# SCH_balcony_pump_2022-12-04.net
KiCad netlist of a schematic drawn in EasyEDA
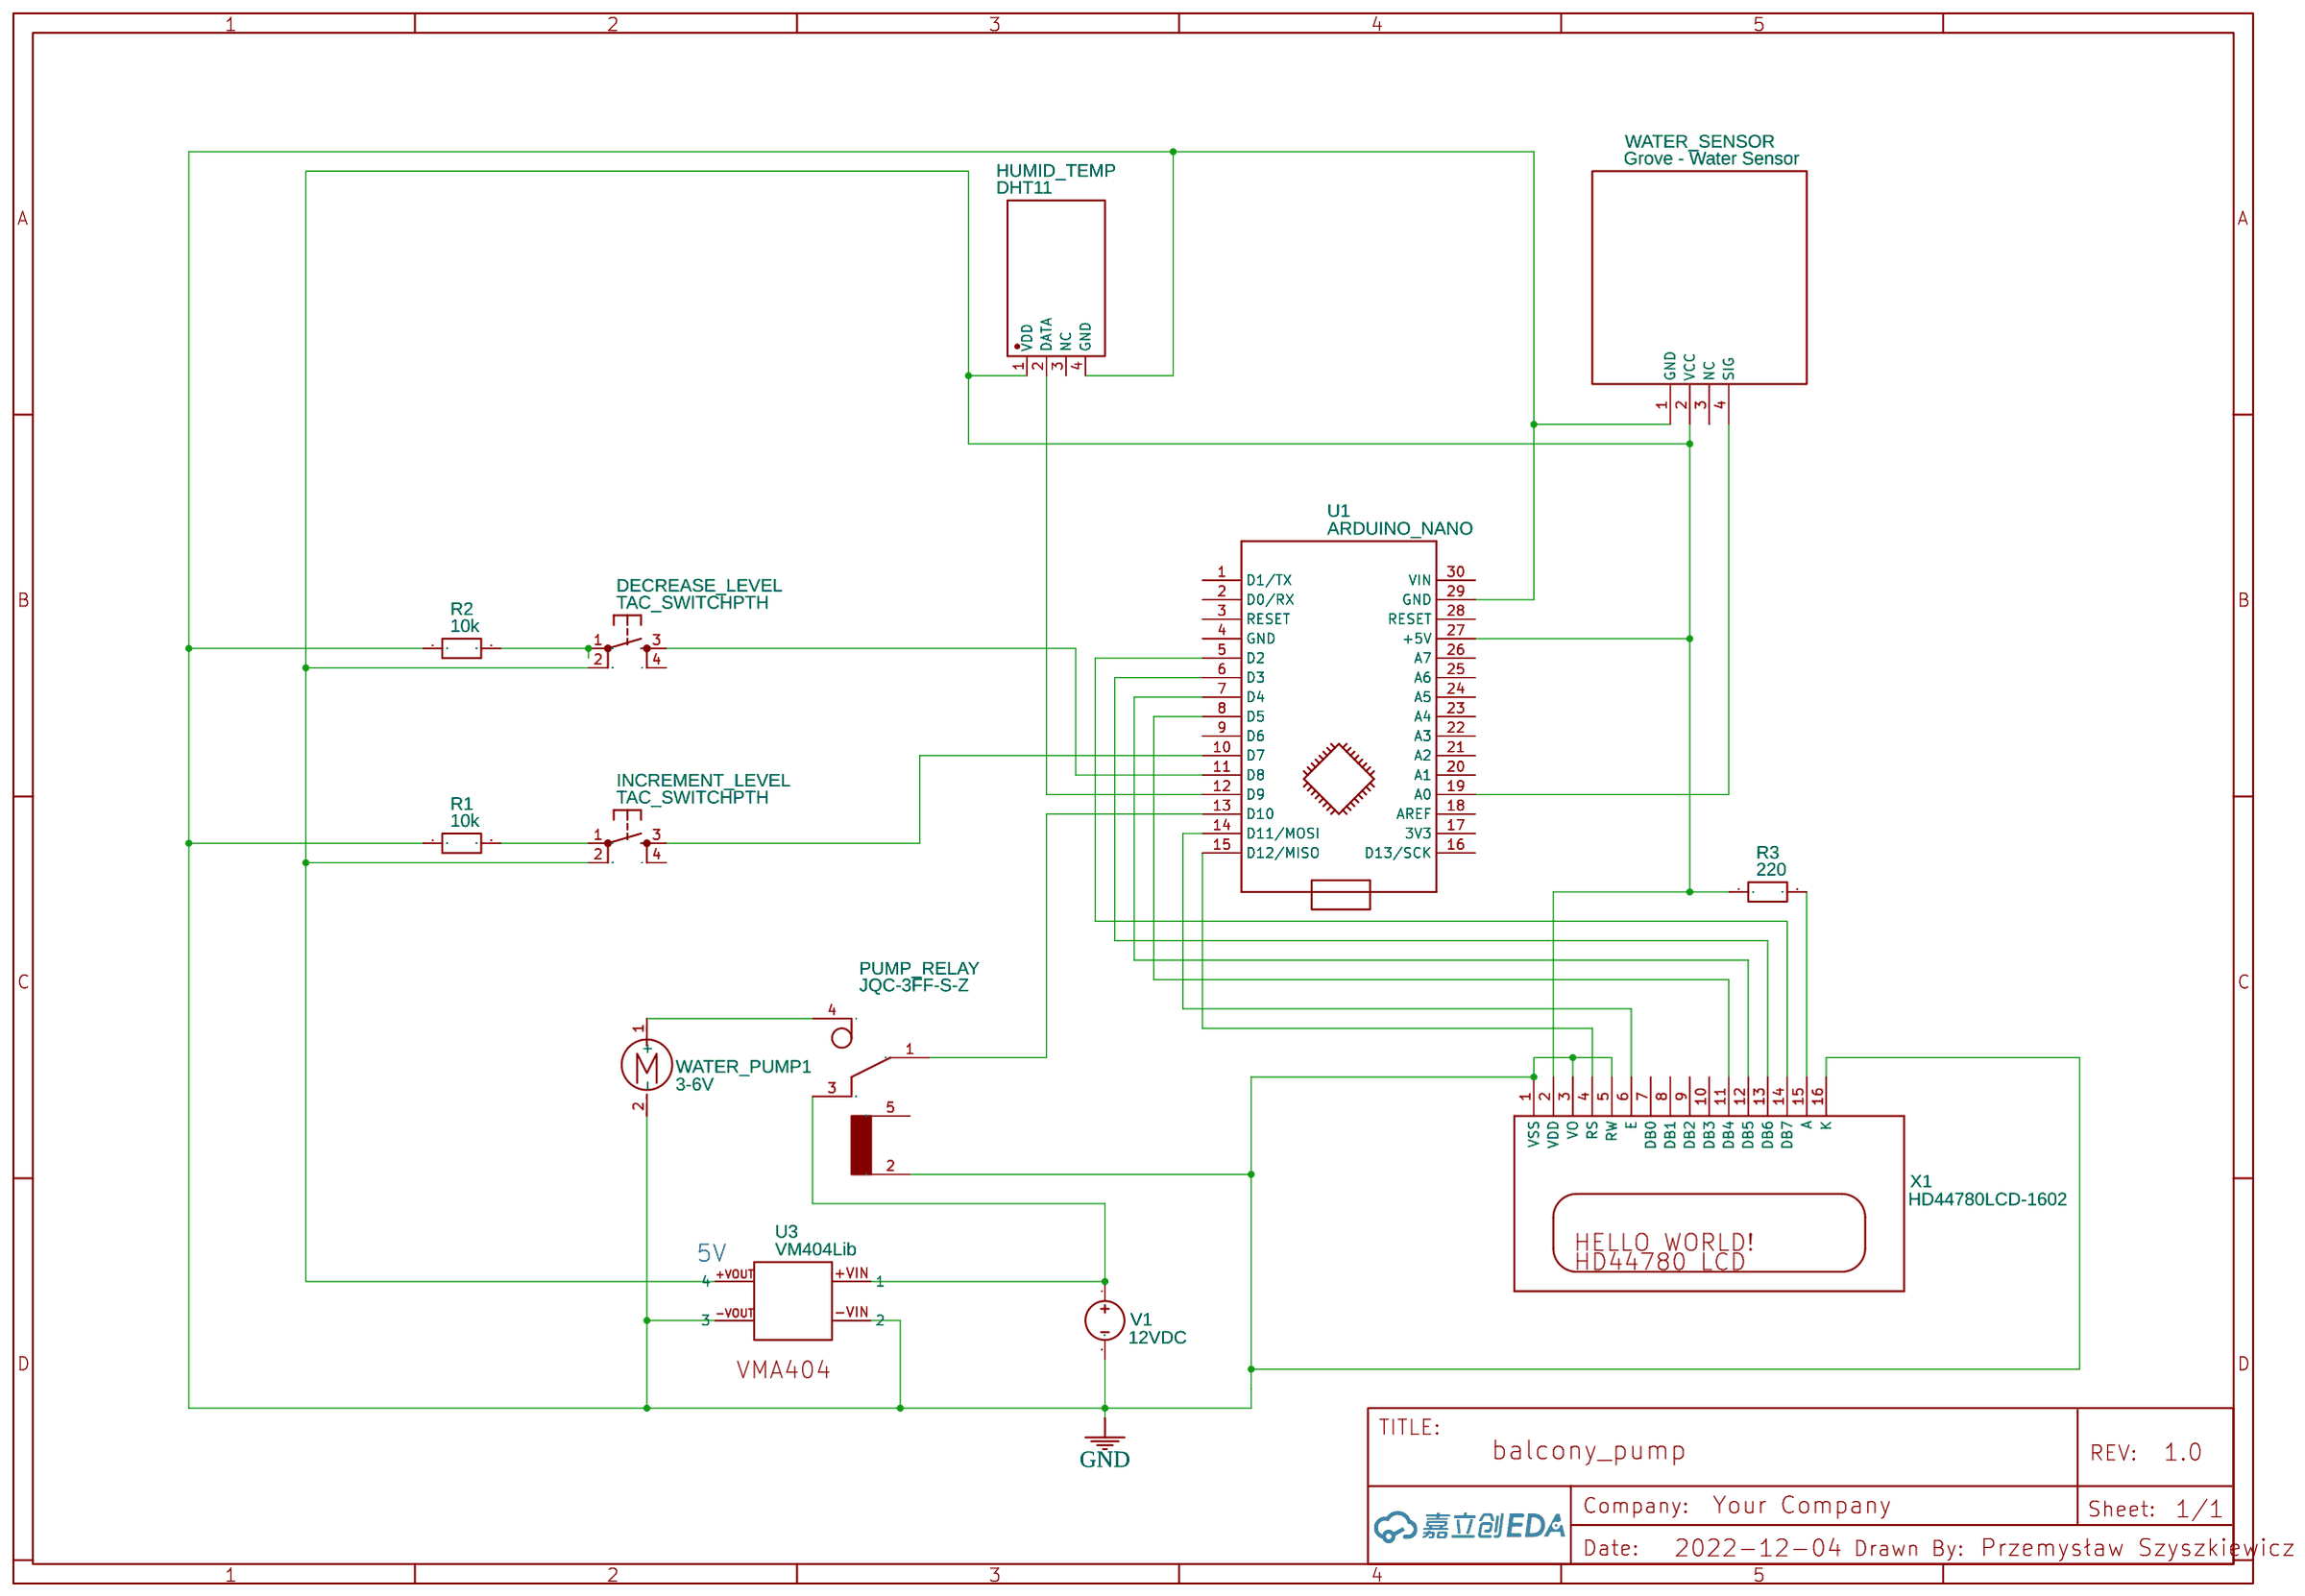
[diagram p0: schematic sheet]

(export (version "E")
  (design (tool "Eeschema 10.0.6"))
  (components
    (comp (ref "DECREASE_LEVEL") (value "TAC_SWITCHPTH") (libsource (lib "") (part "TAC_SWITCHPTH_1")))
    (comp (ref "HUMID_TEMP")
      (value "DHT11")
      (fields (field (name "BOM_Supplier Part") "C117051"))
      (libsource (lib "") (part "DHT11"))
    )
    (comp (ref "INCREMENT_LEVEL") (value "TAC_SWITCHPTH") (libsource (lib "") (part "TAC_SWITCHPTH")))
    (comp (ref "PUMP_RELAY") (value "JQC-3FF-S-Z") (libsource (lib "") (part "JQC-3FF-S-Z")))
    (comp (ref "R1") (value "10k") (libsource (lib "") (part "R_0603_EU")))
    (comp (ref "R2") (value "10k") (libsource (lib "") (part "R_0603_EU")))
    (comp (ref "R3") (value "220") (libsource (lib "") (part "R_0603_EU")))
    (comp (ref "U1") (value "ARDUINO_NANO") (libsource (lib "") (part "ARDUINO_NANO")))
    (comp (ref "U3")
      (value "VM404Lib")
      (fields
        (field (name "BOM_Manufacturer Part") "New SchematicLib")
        (field (name "BOM_Supplier Part") "1612753")
      )
      (libsource (lib "") (part "VM404Lib"))
    )
    (comp (ref "V1") (value "12VDC") (libsource (lib "") (part "Power_Supply_12V")))
    (comp (ref "WATER_PUMP1") (value "3-6V") (libsource (lib "") (part "Motor_DC")))
    (comp (ref "WATER_SENSOR")
      (value "Grove - Water Sensor")
      (fields (field (name "BOM_Supplier Part") "undefined"))
      (libsource (lib "") (part "Grove - Water Sensor"))
    )
    (comp (ref "X1") (value "HD44780LCD-1602") (libsource (lib "") (part "HD44780LCD-1602")))
  )
  (nets
    (net (code "1") (name "GND") (class "Default")
      (node (ref "HUMID_TEMP") (pin "4") (pinfunction "GND_4") (pintype "unspecified"))
      (node (ref "PUMP_RELAY") (pin "2") (pinfunction "2_2") (pintype "unspecified"))
      (node (ref "R1") (pin "1") (pinfunction "1_1") (pintype "unspecified"))
      (node (ref "R2") (pin "1") (pinfunction "1_1") (pintype "unspecified"))
      (node (ref "U1") (pin "29") (pinfunction "GND_29") (pintype "unspecified"))
      (node (ref "U3") (pin "-VIN") (pinfunction "2_-VIN") (pintype "unspecified"))
      (node (ref "U3") (pin "-VOUT") (pinfunction "3_-VOUT") (pintype "unspecified"))
      (node (ref "V1") (pin "2") (pinfunction "2_2") (pintype "unspecified"))
      (node (ref "WATER_PUMP1") (pin "2") (pinfunction "-_2") (pintype "unspecified"))
      (node (ref "WATER_SENSOR") (pin "1") (pinfunction "GND_1") (pintype "unspecified"))
      (node (ref "X1") (pin "1") (pinfunction "VSS_1") (pintype "unspecified"))
      (node (ref "X1") (pin "16") (pinfunction "K_16") (pintype "input"))
      (node (ref "X1") (pin "3") (pinfunction "VO_3") (pintype "input"))
      (node (ref "X1") (pin "5") (pinfunction "RW_5") (pintype "input"))
    )
    (net (code "2") (name "Net-(DECREASE_LEVEL-Pad1)") (class "Default")
      (node (ref "DECREASE_LEVEL") (pin "1") (pinfunction "1_1") (pintype "unspecified"))
      (node (ref "R2") (pin "2") (pinfunction "2_2") (pintype "unspecified"))
    )
    (net (code "3") (name "Net-(HUMID_TEMP-DATA)") (class "Default")
      (node (ref "HUMID_TEMP") (pin "2") (pinfunction "DATA_2") (pintype "unspecified"))
      (node (ref "U1") (pin "12") (pinfunction "D9_12") (pintype "unspecified"))
    )
    (net (code "4") (name "Net-(HUMID_TEMP-VDD)") (class "Default")
      (node (ref "DECREASE_LEVEL") (pin "2") (pinfunction "2_2") (pintype "unspecified"))
      (node (ref "HUMID_TEMP") (pin "1") (pinfunction "VDD_1") (pintype "unspecified"))
      (node (ref "INCREMENT_LEVEL") (pin "2") (pinfunction "2_2") (pintype "unspecified"))
      (node (ref "R3") (pin "1") (pinfunction "1_1") (pintype "unspecified"))
      (node (ref "U1") (pin "27") (pinfunction "+5V_27") (pintype "unspecified"))
      (node (ref "U3") (pin "+VOUT") (pinfunction "4_+VOUT") (pintype "unspecified"))
      (node (ref "WATER_SENSOR") (pin "2") (pinfunction "VCC_2") (pintype "unspecified"))
      (node (ref "X1") (pin "2") (pinfunction "VDD_2") (pintype "unspecified"))
    )
    (net (code "5") (name "Net-(INCREMENT_LEVEL-Pad1)") (class "Default")
      (node (ref "INCREMENT_LEVEL") (pin "1") (pinfunction "1_1") (pintype "unspecified"))
      (node (ref "R1") (pin "2") (pinfunction "2_2") (pintype "unspecified"))
    )
    (net (code "6") (name "Net-(U1-A0)") (class "Default")
      (node (ref "U1") (pin "19") (pinfunction "A0_19") (pintype "unspecified"))
      (node (ref "WATER_SENSOR") (pin "4") (pinfunction "SIG_4") (pintype "unspecified"))
    )
    (net (code "7") (name "Net-(U1-D2)") (class "Default")
      (node (ref "U1") (pin "5") (pinfunction "D2_5") (pintype "unspecified"))
      (node (ref "X1") (pin "14") (pinfunction "DB7_14") (pintype "unspecified"))
    )
    (net (code "8") (name "Net-(U1-D3)") (class "Default")
      (node (ref "U1") (pin "6") (pinfunction "D3_6") (pintype "unspecified"))
      (node (ref "X1") (pin "13") (pinfunction "DB6_13") (pintype "unspecified"))
    )
    (net (code "9") (name "Net-(U1-D4)") (class "Default")
      (node (ref "U1") (pin "7") (pinfunction "D4_7") (pintype "unspecified"))
      (node (ref "X1") (pin "12") (pinfunction "DB5_12") (pintype "unspecified"))
    )
    (net (code "10") (name "Net-(U1-D5)") (class "Default")
      (node (ref "U1") (pin "8") (pinfunction "D5_8") (pintype "unspecified"))
      (node (ref "X1") (pin "11") (pinfunction "DB4_11") (pintype "unspecified"))
    )
    (net (code "11") (name "Net-(U1-D7)") (class "Default")
      (node (ref "INCREMENT_LEVEL") (pin "3") (pinfunction "3_3") (pintype "unspecified"))
      (node (ref "U1") (pin "10") (pinfunction "D7_10") (pintype "unspecified"))
    )
    (net (code "12") (name "Net-(U1-D8)") (class "Default")
      (node (ref "DECREASE_LEVEL") (pin "3") (pinfunction "3_3") (pintype "unspecified"))
      (node (ref "U1") (pin "11") (pinfunction "D8_11") (pintype "unspecified"))
    )
    (net (code "13") (name "Net-(U1-D10)") (class "Default")
      (node (ref "PUMP_RELAY") (pin "1") (pinfunction "1_1") (pintype "unspecified"))
      (node (ref "U1") (pin "13") (pinfunction "D10_13") (pintype "unspecified"))
    )
    (net (code "14") (name "Net-(U1-D11{slash}MOSI)") (class "Default")
      (node (ref "U1") (pin "14") (pinfunction "D11/MOSI_14") (pintype "unspecified"))
      (node (ref "X1") (pin "6") (pinfunction "E_6") (pintype "input"))
    )
    (net (code "15") (name "Net-(U1-D12{slash}MISO)") (class "Default")
      (node (ref "U1") (pin "15") (pinfunction "D12/MISO_15") (pintype "unspecified"))
      (node (ref "X1") (pin "4") (pinfunction "RS_4") (pintype "input"))
    )
    (net (code "16") (name "Net-(U3-1)") (class "Default")
      (node (ref "PUMP_RELAY") (pin "3") (pinfunction "3_3") (pintype "unspecified"))
      (node (ref "U3") (pin "+VIN") (pinfunction "1_+VIN") (pintype "unspecified"))
      (node (ref "V1") (pin "1") (pinfunction "1_1") (pintype "unspecified"))
    )
    (net (code "17") (name "Net-(WATER_PUMP1-+)") (class "Default")
      (node (ref "PUMP_RELAY") (pin "4") (pinfunction "4_4") (pintype "unspecified"))
      (node (ref "WATER_PUMP1") (pin "1") (pinfunction "+_1") (pintype "unspecified"))
    )
    (net (code "18") (name "Net-(X1-A)") (class "Default")
      (node (ref "R3") (pin "2") (pinfunction "2_2") (pintype "unspecified"))
      (node (ref "X1") (pin "15") (pinfunction "A_15") (pintype "input"))
    )
    (net (code "19") (name "unconnected-(DECREASE_LEVEL-Pad4)") (class "Default")
      (node (ref "DECREASE_LEVEL") (pin "4") (pinfunction "4_4") (pintype "unspecified"))
    )
    (net (code "20") (name "unconnected-(HUMID_TEMP-NC-Pad3)") (class "Default")
      (node (ref "HUMID_TEMP") (pin "3") (pinfunction "NC_3") (pintype "unspecified"))
    )
    (net (code "21") (name "unconnected-(INCREMENT_LEVEL-Pad4)") (class "Default")
      (node (ref "INCREMENT_LEVEL") (pin "4") (pinfunction "4_4") (pintype "unspecified"))
    )
    (net (code "22") (name "unconnected-(PUMP_RELAY-Pad5)") (class "Default")
      (node (ref "PUMP_RELAY") (pin "5") (pinfunction "5_5") (pintype "unspecified"))
    )
    (net (code "23") (name "unconnected-(U1-3V3-Pad17)") (class "Default")
      (node (ref "U1") (pin "17") (pinfunction "3V3_17") (pintype "unspecified"))
    )
    (net (code "24") (name "unconnected-(U1-A1-Pad20)") (class "Default")
      (node (ref "U1") (pin "20") (pinfunction "A1_20") (pintype "unspecified"))
    )
    (net (code "25") (name "unconnected-(U1-A2-Pad21)") (class "Default")
      (node (ref "U1") (pin "21") (pinfunction "A2_21") (pintype "unspecified"))
    )
    (net (code "26") (name "unconnected-(U1-A3-Pad22)") (class "Default")
      (node (ref "U1") (pin "22") (pinfunction "A3_22") (pintype "unspecified"))
    )
    (net (code "27") (name "unconnected-(U1-A4-Pad23)") (class "Default")
      (node (ref "U1") (pin "23") (pinfunction "A4_23") (pintype "unspecified"))
    )
    (net (code "28") (name "unconnected-(U1-A5-Pad24)") (class "Default")
      (node (ref "U1") (pin "24") (pinfunction "A5_24") (pintype "unspecified"))
    )
    (net (code "29") (name "unconnected-(U1-A6-Pad25)") (class "Default")
      (node (ref "U1") (pin "25") (pinfunction "A6_25") (pintype "unspecified"))
    )
    (net (code "30") (name "unconnected-(U1-A7-Pad26)") (class "Default")
      (node (ref "U1") (pin "26") (pinfunction "A7_26") (pintype "unspecified"))
    )
    (net (code "31") (name "unconnected-(U1-AREF-Pad18)") (class "Default")
      (node (ref "U1") (pin "18") (pinfunction "AREF_18") (pintype "unspecified"))
    )
    (net (code "32") (name "unconnected-(U1-D0{slash}RX-Pad2)") (class "Default")
      (node (ref "U1") (pin "2") (pinfunction "D0/RX_2") (pintype "unspecified"))
    )
    (net (code "33") (name "unconnected-(U1-D1{slash}TX-Pad1)") (class "Default")
      (node (ref "U1") (pin "1") (pinfunction "D1/TX_1") (pintype "unspecified"))
    )
    (net (code "34") (name "unconnected-(U1-D6-Pad9)") (class "Default")
      (node (ref "U1") (pin "9") (pinfunction "D6_9") (pintype "unspecified"))
    )
    (net (code "35") (name "unconnected-(U1-D13{slash}SCK-Pad16)") (class "Default")
      (node (ref "U1") (pin "16") (pinfunction "D13/SCK_16") (pintype "unspecified"))
    )
    (net (code "36") (name "unconnected-(U1-GND-Pad4)") (class "Default")
      (node (ref "U1") (pin "4") (pinfunction "GND_4") (pintype "unspecified"))
    )
    (net (code "37") (name "unconnected-(U1-RESET-Pad3)") (class "Default")
      (node (ref "U1") (pin "3") (pinfunction "RESET_3") (pintype "unspecified"))
    )
    (net (code "38") (name "unconnected-(U1-RESET-Pad28)") (class "Default")
      (node (ref "U1") (pin "28") (pinfunction "RESET_28") (pintype "unspecified"))
    )
    (net (code "39") (name "unconnected-(U1-VIN-Pad30)") (class "Default")
      (node (ref "U1") (pin "30") (pinfunction "VIN_30") (pintype "unspecified"))
    )
    (net (code "40") (name "unconnected-(WATER_SENSOR-NC-Pad3)") (class "Default")
      (node (ref "WATER_SENSOR") (pin "3") (pinfunction "NC_3") (pintype "unspecified"))
    )
    (net (code "41") (name "unconnected-(X1-DB0-Pad7)") (class "Default")
      (node (ref "X1") (pin "7") (pinfunction "DB0_7") (pintype "unspecified"))
    )
    (net (code "42") (name "unconnected-(X1-DB1-Pad8)") (class "Default")
      (node (ref "X1") (pin "8") (pinfunction "DB1_8") (pintype "unspecified"))
    )
    (net (code "43") (name "unconnected-(X1-DB2-Pad9)") (class "Default")
      (node (ref "X1") (pin "9") (pinfunction "DB2_9") (pintype "unspecified"))
    )
    (net (code "44") (name "unconnected-(X1-DB3-Pad10)") (class "Default")
      (node (ref "X1") (pin "10") (pinfunction "DB3_10") (pintype "unspecified"))
    )
  )
)
